# EGS002.net
KiCad netlist of a schematic drawn in Altium Designer
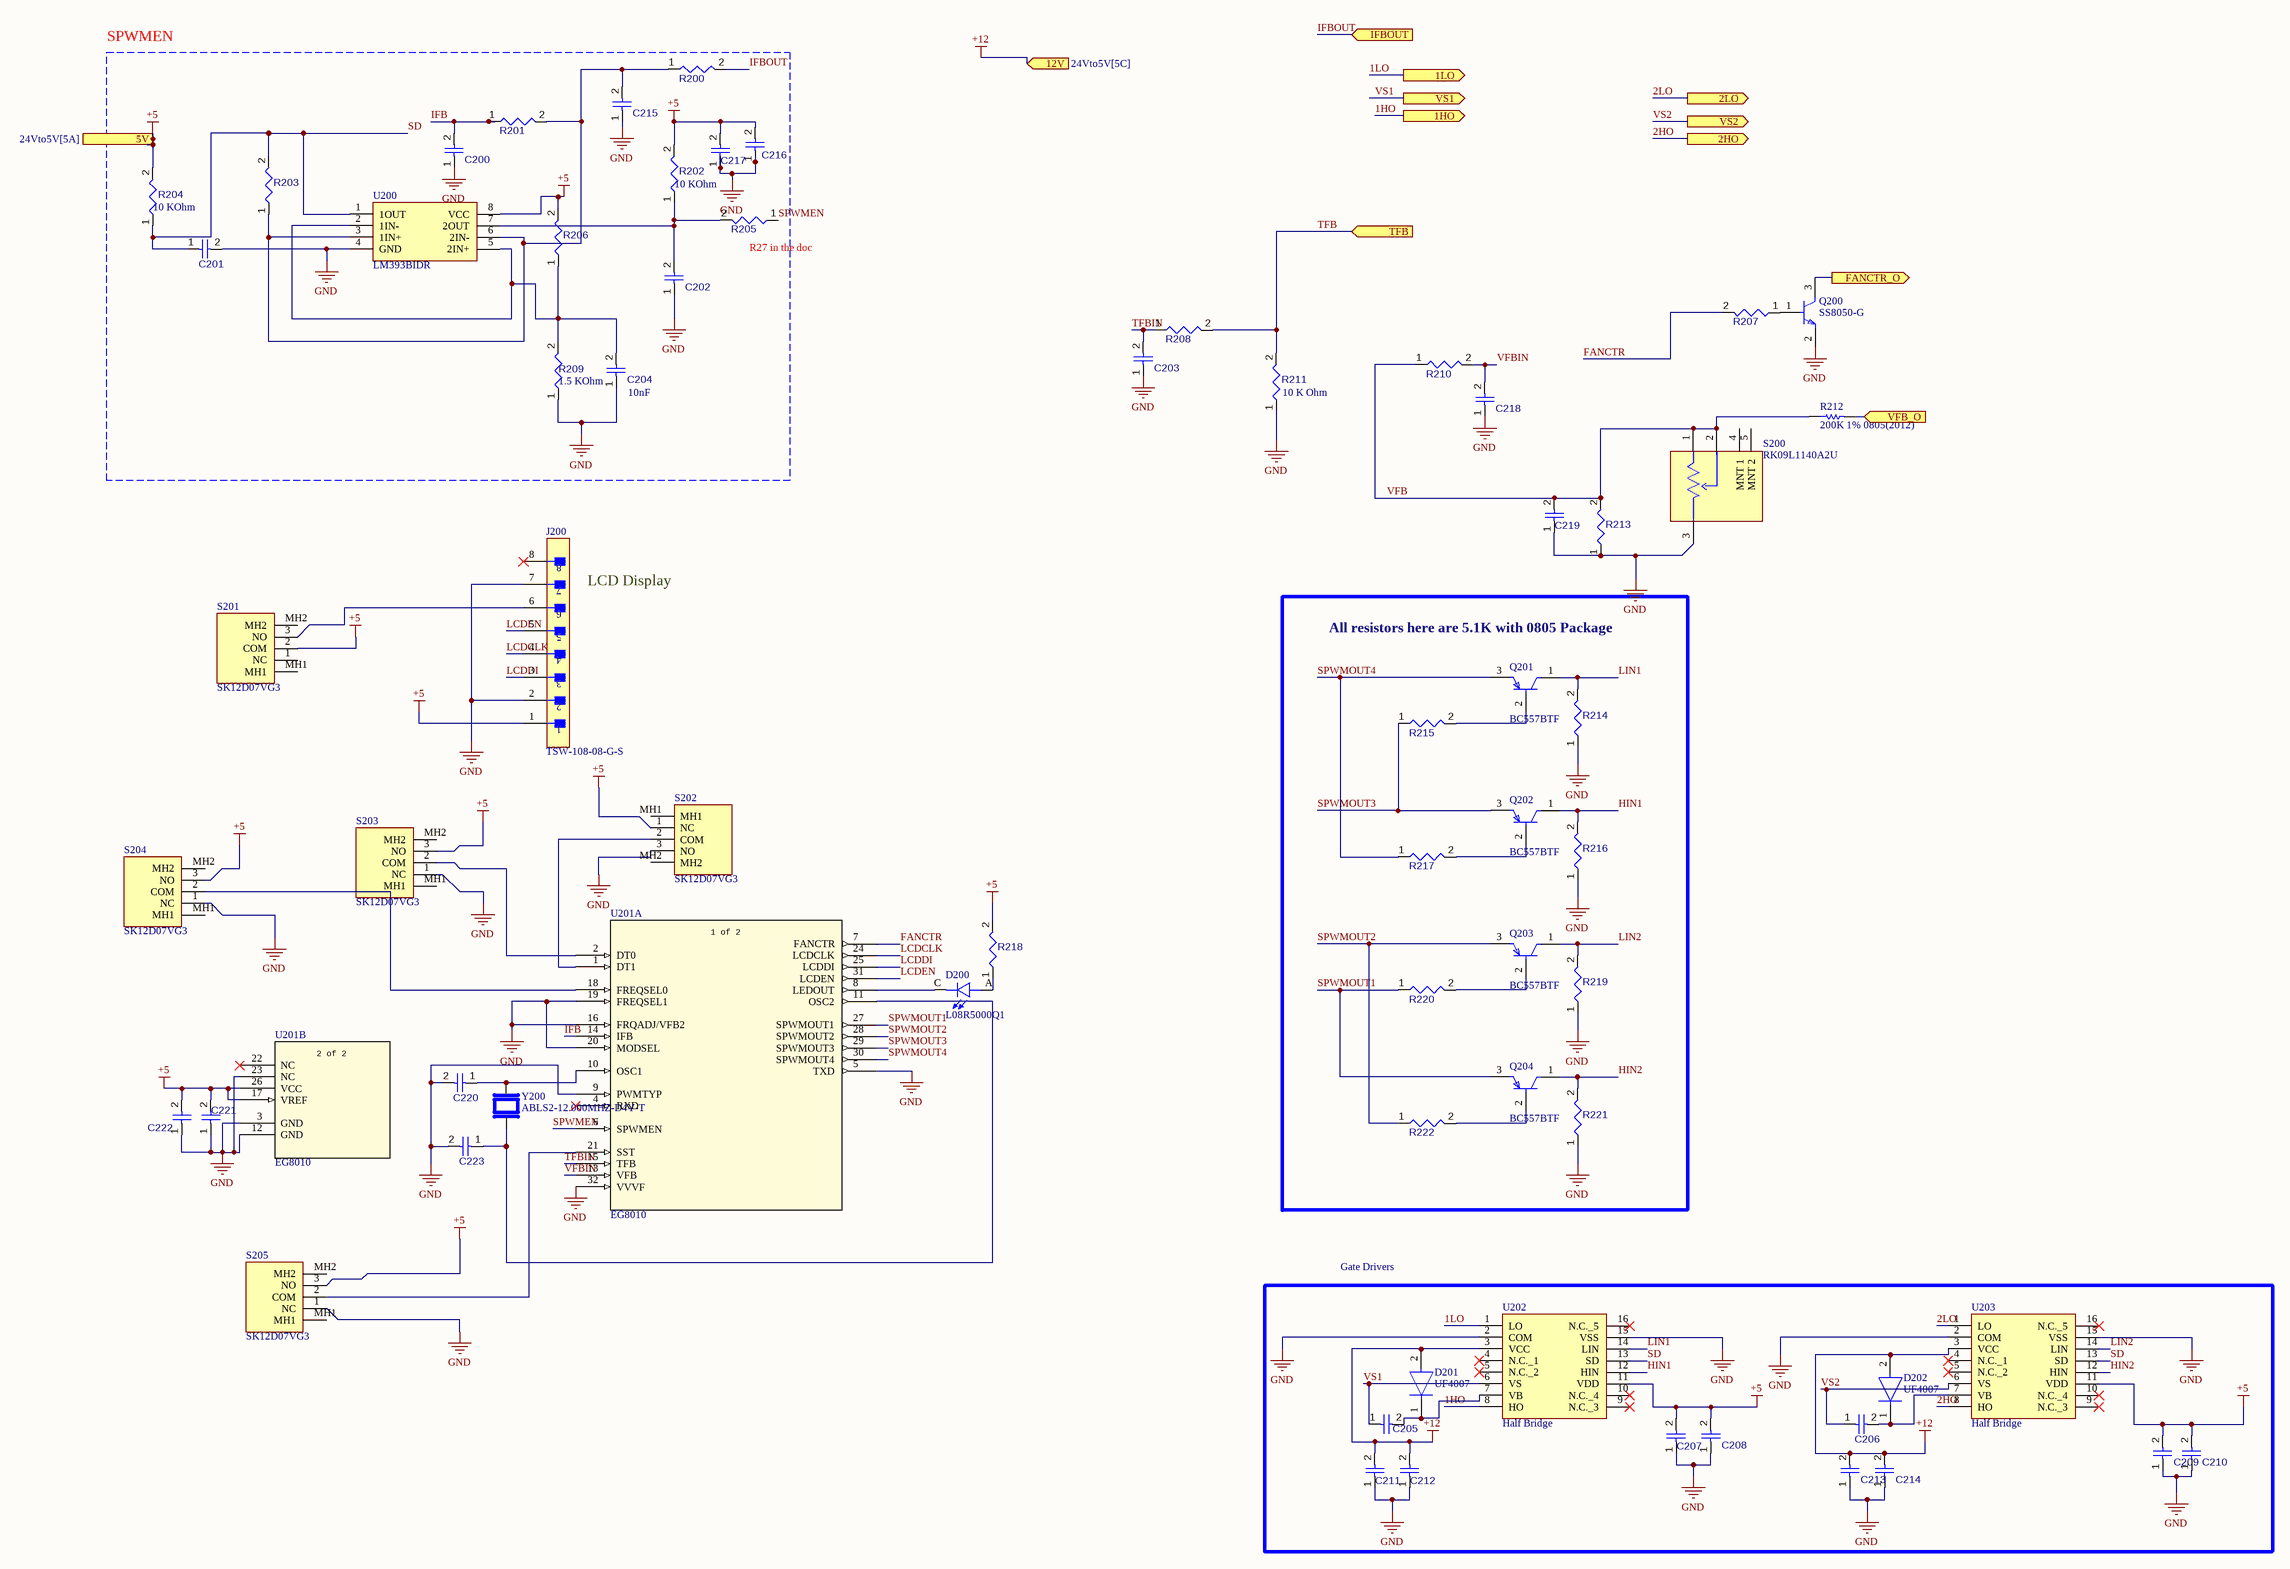
[diagram p0: EGS002.SchDoc]

(export (version "E")
  (design (tool "Eeschema 10.0.6"))
  (components
    (comp (ref "C200")
      (value "Capacitor 10nF +/-20% 50V 0402")
      (footprint "CAPC0402(1005)60_L")
      (description "Chip Capacitor, 10nF +/-20%, 50V, 0402, Thickness 0.6 mm")
      (fields (field (name "TOLERANCE") "5%"))
      (libsource (lib "Rahulb 23") (part "CAP-NP-2"))
    )
    (comp (ref "C201")
      (value "Capacitor 1nF +/-20% 50V 0402")
      (footprint "CAPC0402(1005)33_L")
      (description "Chip Capacitor, 1nF +/-20%, 50V, 0402, Thickness 0.33 mm")
      (fields (field (name "TOLERANCE") "10%"))
      (libsource (lib "Rahulb 23") (part "CAP-NP-2"))
    )
    (comp (ref "C202")
      (value "Capacitor 1nF +/-20% 50V 0402")
      (footprint "CAPC0402(1005)33_L")
      (description "Chip Capacitor, 1nF +/-20%, 50V, 0402, Thickness 0.33 mm")
      (fields (field (name "TOLERANCE") "10%"))
      (libsource (lib "Rahulb 23") (part "CAP-NP-2"))
    )
    (comp (ref "C203")
      (value "Capacitor 100 nF +/-10% 50 V 0805")
      (footprint "CAPC2013X95X50LL10T25")
      (description "Chip Capacitor, 100 nF, +/- 10%, 50 V, 0805 (2012 Metric)")
      (fields (field (name "TOLERANCE") "10%"))
      (libsource (lib "Rahulb 23") (part "CAP-NP-2"))
    )
    (comp (ref "C204")
      (value "Capacitor 10nF +/-20% 50V 0402")
      (footprint "CAPC0402(1005)60_L")
      (description "Chip Capacitor, 10nF +/-20%, 50V, 0402, Thickness 0.6 mm")
      (fields (field (name "TOLERANCE") "5%"))
      (libsource (lib "Rahulb 23") (part "CAP-NP-2"))
    )
    (comp (ref "C205")
      (value "Capacitor 10 uF +/- 10% 16 V 0805")
      (footprint "CAPC2013X135X45NL10T25")
      (description "Chip Capacitor, 10 uF, +/- 10%, 16 V, 0805 (2012 Metric)")
      (fields (field (name "TOLERANCE") "10%"))
      (libsource (lib "Rahulb 23") (part "CAP-NP-2"))
    )
    (comp (ref "C206")
      (value "Capacitor 10 uF +/- 10% 16 V 1206")
      (footprint "CAPC3216X180X50NL20T25")
      (description "Chip Capacitor, 10 uF, +/- 10%, 16 V, 1206 (3216 Metric)")
      (fields (field (name "TOLERANCE") "10%"))
      (libsource (lib "Rahulb 23") (part "CAP-NP-2"))
    )
    (comp (ref "C207")
      (value "Capacitor 100 nF +/-10% 50 V 0805")
      (footprint "CAPC2013X95X50LL10T25")
      (description "Chip Capacitor, 100 nF, +/- 10%, 50 V, 0805 (2012 Metric)")
      (fields (field (name "TOLERANCE") "10%"))
      (libsource (lib "Rahulb 23") (part "CAP-NP-2"))
    )
    (comp (ref "C208")
      (value "Capacitor 10 uF +/- 10% 16 V 1206")
      (footprint "CAPC3216X180X50NL20T25")
      (description "Chip Capacitor, 10 uF, +/- 10%, 16 V, 1206 (3216 Metric)")
      (fields (field (name "TOLERANCE") "10%"))
      (libsource (lib "Rahulb 23") (part "CAP-NP-2"))
    )
    (comp (ref "C209")
      (value "Capacitor 100 nF +/-10% 50 V 0805")
      (footprint "CAPC2013X95X50LL10T25")
      (description "Chip Capacitor, 100 nF, +/- 10%, 50 V, 0805 (2012 Metric)")
      (fields (field (name "TOLERANCE") "10%"))
      (libsource (lib "Rahulb 23") (part "CAP-NP-2"))
    )
    (comp (ref "C210")
      (value "Capacitor 10 uF +/- 10% 16 V 1206")
      (footprint "CAPC3216X180X50NL20T25")
      (description "Chip Capacitor, 10 uF, +/- 10%, 16 V, 1206 (3216 Metric)")
      (fields (field (name "TOLERANCE") "10%"))
      (libsource (lib "Rahulb 23") (part "CAP-NP-2"))
    )
    (comp (ref "C211")
      (value "Capacitor 100 nF +/-10% 50 V 0805")
      (footprint "CAPC2013X95X50LL10T25")
      (description "Chip Capacitor, 100 nF, +/- 10%, 50 V, 0805 (2012 Metric)")
      (fields (field (name "TOLERANCE") "10%"))
      (libsource (lib "Rahulb 23") (part "CAP-NP-2"))
    )
    (comp (ref "C212")
      (value "Capacitor 10 uF +/- 10% 16 V 1206")
      (footprint "CAPC3216X180X50NL20T25")
      (description "Chip Capacitor, 10 uF, +/- 10%, 16 V, 1206 (3216 Metric)")
      (fields (field (name "TOLERANCE") "10%"))
      (libsource (lib "Rahulb 23") (part "CAP-NP-2"))
    )
    (comp (ref "C213")
      (value "Capacitor 100 nF +/-10% 50 V 0805")
      (footprint "CAPC2013X95X50LL10T25")
      (description "Chip Capacitor, 100 nF, +/- 10%, 50 V, 0805 (2012 Metric)")
      (fields (field (name "TOLERANCE") "10%"))
      (libsource (lib "Rahulb 23") (part "CAP-NP-2"))
    )
    (comp (ref "C214")
      (value "Capacitor 10 uF +/- 10% 16 V 1206")
      (footprint "CAPC3216X180X50NL20T25")
      (description "Chip Capacitor, 10 uF, +/- 10%, 16 V, 1206 (3216 Metric)")
      (fields (field (name "TOLERANCE") "10%"))
      (libsource (lib "Rahulb 23") (part "CAP-NP-2"))
    )
    (comp (ref "C215")
      (value "Capacitor 1nF +/-20% 50V 0402")
      (footprint "CAPC0402(1005)33_L")
      (description "Chip Capacitor, 1nF +/-20%, 50V, 0402, Thickness 0.33 mm")
      (fields (field (name "TOLERANCE") "10%"))
      (libsource (lib "Rahulb 23") (part "CAP-NP-2"))
    )
    (comp (ref "C216")
      (value "Capacitor 10 uF +/- 10% 16 V 1206")
      (footprint "CAPC3216X180X50NL20T25")
      (description "Chip Capacitor, 10 uF, +/- 10%, 16 V, 1206 (3216 Metric)")
      (fields (field (name "TOLERANCE") "10%"))
      (libsource (lib "Rahulb 23") (part "CAP-NP-2"))
    )
    (comp (ref "C217")
      (value "Capacitor 100 nF +/-10% 50 V 0805")
      (footprint "CAPC2013X95X50LL10T25")
      (description "Chip Capacitor, 100 nF, +/- 10%, 50 V, 0805 (2012 Metric)")
      (fields (field (name "TOLERANCE") "10%"))
      (libsource (lib "Rahulb 23") (part "CAP-NP-2"))
    )
    (comp (ref "C218")
      (value "Capacitor 100 nF +/-10% 50 V 0805")
      (footprint "CAPC2013X95X50LL10T25")
      (description "Chip Capacitor, 100 nF, +/- 10%, 50 V, 0805 (2012 Metric)")
      (fields (field (name "TOLERANCE") "10%"))
      (libsource (lib "Rahulb 23") (part "CAP-NP-2"))
    )
    (comp (ref "C219")
      (value "Capacitor 100 nF +/-10% 50 V 0805")
      (footprint "CAPC2013X95X50LL10T25")
      (description "Chip Capacitor, 100 nF, +/- 10%, 50 V, 0805 (2012 Metric)")
      (fields (field (name "TOLERANCE") "10%"))
      (libsource (lib "Rahulb 23") (part "CAP-NP-2"))
    )
    (comp (ref "C220")
      (value "Capacitor 22pF +/-10% 50V 0402")
      (footprint "CAPC0402(1005)60_L")
      (description "Chip Capacitor, 22pF +/-10%, 50V, 0402, Thickness 0.6 mm")
      (fields (field (name "TOLERANCE") "10%"))
      (libsource (lib "Rahulb 23") (part "CAP-NP-2"))
    )
    (comp (ref "C221")
      (value "Capacitor 10 uF +/- 10% 16 V 1206")
      (footprint "CAPC3216X180X50NL20T25")
      (description "Chip Capacitor, 10 uF, +/- 10%, 16 V, 1206 (3216 Metric)")
      (fields (field (name "TOLERANCE") "10%"))
      (libsource (lib "Rahulb 23") (part "CAP-NP-2"))
    )
    (comp (ref "C222")
      (value "Capacitor 100 nF +/-10% 50 V 0805")
      (footprint "CAPC2013X95X50LL10T25")
      (description "Chip Capacitor, 100 nF, +/- 10%, 50 V, 0805 (2012 Metric)")
      (fields (field (name "TOLERANCE") "10%"))
      (libsource (lib "Rahulb 23") (part "CAP-NP-2"))
    )
    (comp (ref "C223")
      (value "Capacitor 22pF +/-10% 50V 0402")
      (footprint "CAPC0402(1005)60_L")
      (description "Chip Capacitor, 22pF +/-10%, 50V, 0402, Thickness 0.6 mm")
      (fields (field (name "TOLERANCE") "10%"))
      (libsource (lib "Rahulb 23") (part "CAP-NP-2"))
    )
    (comp (ref "D200")
      (value "L08R5000Q1")
      (footprint "LEDRD254W57D500H1070")
      (fields (field (name "MF") "LED Technology"))
      (libsource (lib "myComponents") (part "L08R5000Q1"))
    )
    (comp (ref "D201")
      (value "UF4007")
      (footprint "FP-017AH-MFG")
      (description "DIODE GEN PURP 1KV 1A DO41")
      (fields
        (field (name "MANUFACTURER") "ON Semiconductor")
        (field (name "OCTOPART") "https://octopart.com/uf4007-on+semiconductor-84331693")
      )
      (libsource (lib "Altium Content Vault") (part "d7152d700b627762746794eb795d46e"))
    )
    (comp (ref "D202")
      (value "UF4007")
      (footprint "FP-017AH-MFG")
      (description "DIODE GEN PURP 1KV 1A DO41")
      (fields
        (field (name "MANUFACTURER") "ON Semiconductor")
        (field (name "OCTOPART") "https://octopart.com/uf4007-on+semiconductor-84331693")
      )
      (libsource (lib "Altium Content Vault") (part "d7152d700b627762746794eb795d46e"))
    )
    (comp (ref "J200")
      (value "TSW-108-08-G-S")
      (footprint "FP-TSW-108-08-G-S-MFG")
      (description "CONN HEADER VERT 8POS 2.54MM")
      (fields
        (field (name "MANUFACTURER") "Samtec")
        (field (name "OCTOPART") "https://octopart.com/tsw-108-08-g-s-samtec-272653")
      )
      (libsource (lib "Altium Content Vault") (part "99ec2b232beb5d2356d4d77f6a047f0"))
    )
    (comp (ref "Q200")
      (value "SS8050-G")
      (footprint "FP-SS8050-G-MFG")
      (description "NPN TRANSISTOR 1.5A 40V SOT-23 R")
      (libsource (lib "Altium Content Vault") (part "2a1388f82443b098dcd57d24ac7632d"))
    )
    (comp (ref "Q201")
      (value "BC557BTF")
      (footprint "FP-135AR-MFG")
      (description "BC557BTF Small Signal Bipolar Transistor, 0.1A I(C), 45V V(BR)CEO, 1-Element, PNP, Silicon, TO-92")
      (libsource (lib "Altium Content Vault") (part "9e2844d3eb996af6824d2c99fe21afc"))
    )
    (comp (ref "Q202")
      (value "BC557BTF")
      (footprint "FP-135AR-MFG")
      (description "BC557BTF Small Signal Bipolar Transistor, 0.1A I(C), 45V V(BR)CEO, 1-Element, PNP, Silicon, TO-92")
      (libsource (lib "Altium Content Vault") (part "9e2844d3eb996af6824d2c99fe21afc"))
    )
    (comp (ref "Q203")
      (value "BC557BTF")
      (footprint "FP-135AR-MFG")
      (description "BC557BTF Small Signal Bipolar Transistor, 0.1A I(C), 45V V(BR)CEO, 1-Element, PNP, Silicon, TO-92")
      (libsource (lib "Altium Content Vault") (part "9e2844d3eb996af6824d2c99fe21afc"))
    )
    (comp (ref "Q204")
      (value "BC557BTF")
      (footprint "FP-135AR-MFG")
      (description "BC557BTF Small Signal Bipolar Transistor, 0.1A I(C), 45V V(BR)CEO, 1-Element, PNP, Silicon, TO-92")
      (libsource (lib "Altium Content Vault") (part "9e2844d3eb996af6824d2c99fe21afc"))
    )
    (comp (ref "R200")
      (value "Resistor 1K +/-5% 0805 125 mW")
      (footprint "RESC0805(2012)_L")
      (description "Chip Resistor, 1 kOhms, +/-5%, 125 mW, -55 to 155 degC, 0805")
      (fields (field (name "TOLERANCE") "5%") (field (name "POWER") "125mW"))
      (libsource (lib "Rahulb 23") (part "RES-2"))
    )
    (comp (ref "R201")
      (value "Resistor 100k +/-1% 0805 125 mW")
      (footprint "RESC2013X70X40ML20T20")
      (description "Chip Resistor, 100 KOhm, +/- 1%, 0.125 W, -55 to 155 degC, 0805 (2012 Metric)")
      (fields (field (name "TOLERANCE") "1%") (field (name "POWER") "125mW"))
      (libsource (lib "Rahulb 23") (part "RES-2"))
    )
    (comp (ref "R202")
      (value "Resistor 10k +/-1% 0805 125 mW")
      (footprint "RESC2013X50X35ML15T15")
      (description "Chip Resistor, 10 KOhm, +/- 1%, 125 mW, -55 to 155 degC, 0805 (2012 Metric)")
      (fields (field (name "TOLERANCE") "1%") (field (name "POWER") "125mW"))
      (libsource (lib "Rahulb 23") (part "RES-2"))
    )
    (comp (ref "R203")
      (value "Resistor 100k +/-1% 0805 125 mW")
      (footprint "RESC2013X70X40ML20T20")
      (description "Chip Resistor, 100 KOhm, +/- 1%, 0.125 W, -55 to 155 degC, 0805 (2012 Metric)")
      (fields (field (name "TOLERANCE") "1%") (field (name "POWER") "125mW"))
      (libsource (lib "Rahulb 23") (part "RES-2"))
    )
    (comp (ref "R204")
      (value "Resistor 10k +/-1% 0805 125 mW")
      (footprint "RESC2013X50X35ML15T15")
      (description "Chip Resistor, 10 KOhm, +/- 1%, 125 mW, -55 to 155 degC, 0805 (2012 Metric)")
      (fields (field (name "TOLERANCE") "1%") (field (name "POWER") "125mW"))
      (libsource (lib "Rahulb 23") (part "RES-2"))
    )
    (comp (ref "R205")
      (value "Resistor 1.5k +/-1% 0805 125 mW")
      (footprint "RESC2013X50X35ML15T15")
      (description "Chip Resistor, 1.5 KOhm, +/- 1%, 125 mW, -55 to 155 degC, 0805 (2012 Metric)")
      (fields (field (name "TOLERANCE") "1%") (field (name "POWER") "125mW"))
      (libsource (lib "Rahulb 23") (part "RES-2"))
    )
    (comp (ref "R206")
      (value "Resistor 10k +/-1% 0805 125 mW")
      (footprint "RESC2013X50X35ML15T15")
      (description "Chip Resistor, 10 KOhm, +/- 1%, 125 mW, -55 to 155 degC, 0805 (2012 Metric)")
      (fields (field (name "TOLERANCE") "1%") (field (name "POWER") "125mW"))
      (libsource (lib "Rahulb 23") (part "RES-2"))
    )
    (comp (ref "R207")
      (value "Resistor 1.5k +/-1% 0805 125 mW")
      (footprint "RESC2013X50X35ML15T15")
      (description "Chip Resistor, 1.5 KOhm, +/- 1%, 125 mW, -55 to 155 degC, 0805 (2012 Metric)")
      (fields (field (name "TOLERANCE") "1%") (field (name "POWER") "125mW"))
      (libsource (lib "Rahulb 23") (part "RES-2"))
    )
    (comp (ref "R208")
      (value "Resistor 100R +/-1 % 0402 63 mW")
      (footprint "RESC0402(1005)_L")
      (description "Chip Resistor, 100 Ohms, +/-1 %, 63 mW, -55 to 155 degC, 0402")
      (fields (field (name "TOLERANCE") "1%") (field (name "POWER") "63mW"))
      (libsource (lib "Rahulb 23") (part "RES-2"))
    )
    (comp (ref "R209")
      (value "Resistor 1.5k +/-1% 0805 125 mW")
      (footprint "RESC2013X50X35ML15T15")
      (description "Chip Resistor, 1.5 KOhm, +/- 1%, 125 mW, -55 to 155 degC, 0805 (2012 Metric)")
      (fields (field (name "TOLERANCE") "1%") (field (name "POWER") "125mW"))
      (libsource (lib "Rahulb 23") (part "RES-2"))
    )
    (comp (ref "R210")
      (value "Resistor 100R +/-1 % 0402 63 mW")
      (footprint "RESC0402(1005)_L")
      (description "Chip Resistor, 100 Ohms, +/-1 %, 63 mW, -55 to 155 degC, 0402")
      (fields (field (name "TOLERANCE") "1%") (field (name "POWER") "63mW"))
      (libsource (lib "Rahulb 23") (part "RES-2"))
    )
    (comp (ref "R211")
      (value "Resistor 10k +/-1% 0805 125 mW")
      (footprint "RESC2013X50X35ML15T15")
      (description "Chip Resistor, 10 KOhm, +/- 1%, 125 mW, -55 to 155 degC, 0805 (2012 Metric)")
      (fields (field (name "TOLERANCE") "1%") (field (name "POWER") "125mW"))
      (libsource (lib "Rahulb 23") (part "RES-2"))
    )
    (comp (ref "R212")
      (value "200K 1% 0805(2012)")
      (footprint "RESC0805(2012)_N")
      (description "200K 0.125W 1% 0805 (2012 Metric)  SMD")
      (fields (field (name "POWER") "0.125 W") (field (name "TOLERANCE") "1 %"))
      (libsource (lib "Altium Content Vault") (part "RES"))
    )
    (comp (ref "R213")
      (value "Resistor 10k +/-1% 0805 125 mW")
      (footprint "RESC2013X50X35ML15T15")
      (description "Chip Resistor, 10 KOhm, +/- 1%, 125 mW, -55 to 155 degC, 0805 (2012 Metric)")
      (fields (field (name "TOLERANCE") "1%") (field (name "POWER") "125mW"))
      (libsource (lib "Rahulb 23") (part "RES-2"))
    )
    (comp (ref "R214")
      (value "Resistor 5.1k +/-1% 0805 125 mW")
      (footprint "RESC2013X50X35ML15T15")
      (description "Chip Resistor, 5.1 KOhm, +/- 1%, 125 mW, -55 to 155 degC, 0805 (2012 Metric)")
      (fields (field (name "TOLERANCE") "1%") (field (name "POWER") "125mW"))
      (libsource (lib "Rahulb 23") (part "RES-2"))
    )
    (comp (ref "R215")
      (value "Resistor 5.1k +/-1% 0805 125 mW")
      (footprint "RESC2013X50X35ML15T15")
      (description "Chip Resistor, 5.1 KOhm, +/- 1%, 125 mW, -55 to 155 degC, 0805 (2012 Metric)")
      (fields (field (name "TOLERANCE") "1%") (field (name "POWER") "125mW"))
      (libsource (lib "Rahulb 23") (part "RES-2"))
    )
    (comp (ref "R216")
      (value "Resistor 5.1k +/-1% 0805 125 mW")
      (footprint "RESC2013X50X35ML15T15")
      (description "Chip Resistor, 5.1 KOhm, +/- 1%, 125 mW, -55 to 155 degC, 0805 (2012 Metric)")
      (fields (field (name "TOLERANCE") "1%") (field (name "POWER") "125mW"))
      (libsource (lib "Rahulb 23") (part "RES-2"))
    )
    (comp (ref "R217")
      (value "Resistor 5.1k +/-1% 0805 125 mW")
      (footprint "RESC2013X50X35ML15T15")
      (description "Chip Resistor, 5.1 KOhm, +/- 1%, 125 mW, -55 to 155 degC, 0805 (2012 Metric)")
      (fields (field (name "TOLERANCE") "1%") (field (name "POWER") "125mW"))
      (libsource (lib "Rahulb 23") (part "RES-2"))
    )
    (comp (ref "R218")
      (value "Resistor 1K +/-5% 0805 125 mW")
      (footprint "RESC0805(2012)_L")
      (description "Chip Resistor, 1 kOhms, +/-5%, 125 mW, -55 to 155 degC, 0805")
      (fields (field (name "TOLERANCE") "5%") (field (name "POWER") "125mW"))
      (libsource (lib "Rahulb 23") (part "RES-2"))
    )
    (comp (ref "R219")
      (value "Resistor 5.1k +/-1% 0805 125 mW")
      (footprint "RESC2013X50X35ML15T15")
      (description "Chip Resistor, 5.1 KOhm, +/- 1%, 125 mW, -55 to 155 degC, 0805 (2012 Metric)")
      (fields (field (name "TOLERANCE") "1%") (field (name "POWER") "125mW"))
      (libsource (lib "Rahulb 23") (part "RES-2"))
    )
    (comp (ref "R220")
      (value "Resistor 5.1k +/-1% 0805 125 mW")
      (footprint "RESC2013X50X35ML15T15")
      (description "Chip Resistor, 5.1 KOhm, +/- 1%, 125 mW, -55 to 155 degC, 0805 (2012 Metric)")
      (fields (field (name "TOLERANCE") "1%") (field (name "POWER") "125mW"))
      (libsource (lib "Rahulb 23") (part "RES-2"))
    )
    (comp (ref "R221")
      (value "Resistor 5.1k +/-1% 0805 125 mW")
      (footprint "RESC2013X50X35ML15T15")
      (description "Chip Resistor, 5.1 KOhm, +/- 1%, 125 mW, -55 to 155 degC, 0805 (2012 Metric)")
      (fields (field (name "TOLERANCE") "1%") (field (name "POWER") "125mW"))
      (libsource (lib "Rahulb 23") (part "RES-2"))
    )
    (comp (ref "R222")
      (value "Resistor 5.1k +/-1% 0805 125 mW")
      (footprint "RESC2013X50X35ML15T15")
      (description "Chip Resistor, 5.1 KOhm, +/- 1%, 125 mW, -55 to 155 degC, 0805 (2012 Metric)")
      (fields (field (name "TOLERANCE") "1%") (field (name "POWER") "125mW"))
      (libsource (lib "Rahulb 23") (part "RES-2"))
    )
    (comp (ref "S200")
      (value "RK09L1140A2U")
      (footprint "FP-RK09L1140A2U-MFG")
      (description "9mm Size Metal Shaft Snap-in Type RK09L Series")
      (fields
        (field (name "TOLERANCE") "20%")
        (field (name "OCTOPART") "https://octopart.com/rk09l1140a2u-alps-7850070")
      )
      (libsource (lib "Altium Content Vault") (part "0c568a6e0ac31b8b52ae5f6704acd43"))
    )
    (comp (ref "S201")
      (value "SK12D07VG3")
      (footprint "SamacSys:SK12D07VG3")
      (description "Switch")
      (libsource (lib "*") (part "SK12D07VG3"))
    )
    (comp (ref "S202")
      (value "SK12D07VG3")
      (footprint "SamacSys:SK12D07VG3")
      (description "Switch")
      (libsource (lib "") (part "SK12D07VG3_1"))
    )
    (comp (ref "S203")
      (value "SK12D07VG3")
      (footprint "SamacSys:SK12D07VG3")
      (description "Switch")
      (libsource (lib "*") (part "SK12D07VG3"))
    )
    (comp (ref "S204")
      (value "SK12D07VG3")
      (footprint "SamacSys:SK12D07VG3")
      (description "Switch")
      (libsource (lib "*") (part "SK12D07VG3"))
    )
    (comp (ref "S205")
      (value "SK12D07VG3")
      (footprint "SamacSys:SK12D07VG3")
      (description "Switch")
      (libsource (lib "*") (part "SK12D07VG3"))
    )
    (comp (ref "U200")
      (value "LM393BIDR")
      (description "Analog Comparators Dual standard comparator 8-SOIC -40 to 85")
      (fields (field (name "MOUSER PART NUMBER") "595-LM393BIDR"))
      (libsource (lib "myComponents") (part "LM393BIDR"))
    )
    (comp (ref "U201")
      (value "EG8010")
      (description "Description")
      (fields (field (name "COPYRIGHT") "Copyright (C) 2026 Ultra Librarian. All rights reserved."))
      (libsource (lib "myComponents") (part "EG8010"))
    )
    (comp (ref "U202")
      (value "Half Bridge")
      (footprint "IR2110S")
      (libsource (lib "myComponents") (part "IR2110S"))
    )
    (comp (ref "U203")
      (value "Half Bridge")
      (footprint "IR2110S")
      (libsource (lib "myComponents") (part "IR2110S"))
    )
    (comp (ref "Y200")
      (value "ABLS2-12.000MHZ-D4Y-T")
      (footprint "XTAL_ABLS2-12.000MHZ-D4Y-T")
      (description "HC/49US (AT49) LOW PROFILE SURFACE MOUNT MICROPROCESSOR CRYSTAL")
      (fields (field (name "MF") "Abracon"))
      (libsource (lib "myComponents") (part "ABLS2-12.000MHZ-D4Y-T"))
    )
  )
  (nets
    (net (code "1") (name "+5") (class "Default")
      (node (ref "C207") (pin "2") (pinfunction "2_2") (pintype "passive"))
      (node (ref "C208") (pin "2") (pinfunction "2_2") (pintype "passive"))
      (node (ref "C209") (pin "2") (pinfunction "2_2") (pintype "passive"))
      (node (ref "C210") (pin "2") (pinfunction "2_2") (pintype "passive"))
      (node (ref "C216") (pin "2") (pinfunction "2_2") (pintype "passive"))
      (node (ref "C217") (pin "2") (pinfunction "2_2") (pintype "passive"))
      (node (ref "C221") (pin "2") (pinfunction "2_2") (pintype "passive"))
      (node (ref "C222") (pin "2") (pinfunction "2_2") (pintype "passive"))
      (node (ref "J200") (pin "1") (pinfunction "1_1") (pintype "passive"))
      (node (ref "R202") (pin "2") (pinfunction "2_2") (pintype "passive"))
      (node (ref "R204") (pin "2") (pinfunction "2_2") (pintype "passive"))
      (node (ref "R206") (pin "2") (pinfunction "2_2") (pintype "passive"))
      (node (ref "R218") (pin "2") (pinfunction "2_2") (pintype "passive"))
      (node (ref "S201") (pin "2") (pinfunction "COM_2") (pintype "passive"))
      (node (ref "S202") (pin "1") (pinfunction "NC_1") (pintype "passive"))
      (node (ref "S203") (pin "3") (pinfunction "NO_3") (pintype "passive"))
      (node (ref "S204") (pin "3") (pinfunction "NO_3") (pintype "passive"))
      (node (ref "S205") (pin "3") (pinfunction "NO_3") (pintype "passive"))
      (node (ref "U200") (pin "8") (pinfunction "VCC_8") (pintype "passive"))
      (node (ref "U201") (pin "17") (pinfunction "VREF_17") (pintype "input"))
      (node (ref "U201") (pin "26") (pinfunction "VCC_26") (pintype "power_in"))
      (node (ref "U202") (pin "11") (pinfunction "VDD_11") (pintype "passive"))
      (node (ref "U203") (pin "11") (pinfunction "VDD_11") (pintype "passive"))
    )
    (net (code "2") (name "+12") (class "Default")
      (node (ref "C211") (pin "2") (pinfunction "2_2") (pintype "passive"))
      (node (ref "C212") (pin "2") (pinfunction "2_2") (pintype "passive"))
      (node (ref "C213") (pin "2") (pinfunction "2_2") (pintype "passive"))
      (node (ref "C214") (pin "2") (pinfunction "2_2") (pintype "passive"))
      (node (ref "D201") (pin "2") (pinfunction "A_2") (pintype "passive"))
      (node (ref "D202") (pin "2") (pinfunction "A_2") (pintype "passive"))
      (node (ref "U202") (pin "3") (pinfunction "VCC_3") (pintype "passive"))
      (node (ref "U203") (pin "3") (pinfunction "VCC_3") (pintype "passive"))
    )
    (net (code "3") (name "/1HO") (class "Default")
      (node (ref "U202") (pin "8") (pinfunction "HO_8") (pintype "passive"))
    )
    (net (code "4") (name "/1LO") (class "Default")
      (node (ref "U202") (pin "1") (pinfunction "LO_1") (pintype "passive"))
    )
    (net (code "5") (name "/2HO") (class "Default")
      (node (ref "U203") (pin "8") (pinfunction "HO_8") (pintype "passive"))
    )
    (net (code "6") (name "/2LO") (class "Default")
      (node (ref "U203") (pin "1") (pinfunction "LO_1") (pintype "passive"))
    )
    (net (code "7") (name "/FANCTR") (class "Default")
      (node (ref "R207") (pin "2") (pinfunction "2_2") (pintype "passive"))
      (node (ref "U201") (pin "7") (pinfunction "FANCTR_7") (pintype "output"))
    )
    (net (code "8") (name "/FANCTR_O") (class "Default")
      (node (ref "Q200") (pin "3") (pinfunction "C_3") (pintype "passive"))
    )
    (net (code "9") (name "/HIN1") (class "Default")
      (node (ref "Q202") (pin "1") (pinfunction "C_1") (pintype "passive"))
      (node (ref "R216") (pin "2") (pinfunction "2_2") (pintype "passive"))
      (node (ref "U202") (pin "12") (pinfunction "HIN_12") (pintype "passive"))
    )
    (net (code "10") (name "/HIN2") (class "Default")
      (node (ref "Q204") (pin "1") (pinfunction "C_1") (pintype "passive"))
      (node (ref "R221") (pin "2") (pinfunction "2_2") (pintype "passive"))
      (node (ref "U203") (pin "12") (pinfunction "HIN_12") (pintype "passive"))
    )
    (net (code "11") (name "/IFB") (class "Default")
      (node (ref "C200") (pin "2") (pinfunction "2_2") (pintype "passive"))
      (node (ref "R201") (pin "1") (pinfunction "1_1") (pintype "passive"))
      (node (ref "U201") (pin "14") (pinfunction "IFB_14") (pintype "input"))
    )
    (net (code "12") (name "/IFBOUT") (class "Default")
      (node (ref "R200") (pin "2") (pinfunction "2_2") (pintype "passive"))
    )
    (net (code "13") (name "/LCDCLK") (class "Default")
      (node (ref "J200") (pin "4") (pinfunction "4_4") (pintype "passive"))
      (node (ref "U201") (pin "24") (pinfunction "LCDCLK_24") (pintype "output"))
    )
    (net (code "14") (name "/LCDDI") (class "Default")
      (node (ref "J200") (pin "3") (pinfunction "3_3") (pintype "passive"))
      (node (ref "U201") (pin "25") (pinfunction "LCDDI_25") (pintype "output"))
    )
    (net (code "15") (name "/LCDEN") (class "Default")
      (node (ref "J200") (pin "5") (pinfunction "5_5") (pintype "passive"))
      (node (ref "U201") (pin "31") (pinfunction "LCDEN_31") (pintype "output"))
    )
    (net (code "16") (name "/LIN1") (class "Default")
      (node (ref "Q201") (pin "1") (pinfunction "C_1") (pintype "passive"))
      (node (ref "R214") (pin "2") (pinfunction "2_2") (pintype "passive"))
      (node (ref "U202") (pin "14") (pinfunction "LIN_14") (pintype "passive"))
    )
    (net (code "17") (name "/LIN2") (class "Default")
      (node (ref "Q203") (pin "1") (pinfunction "C_1") (pintype "passive"))
      (node (ref "R219") (pin "2") (pinfunction "2_2") (pintype "passive"))
      (node (ref "U203") (pin "14") (pinfunction "LIN_14") (pintype "passive"))
    )
    (net (code "18") (name "/SD") (class "Default")
      (node (ref "C201") (pin "1") (pinfunction "1_1") (pintype "passive"))
      (node (ref "R203") (pin "2") (pinfunction "2_2") (pintype "passive"))
      (node (ref "R204") (pin "1") (pinfunction "1_1") (pintype "passive"))
      (node (ref "U200") (pin "1") (pinfunction "1OUT_1") (pintype "passive"))
      (node (ref "U202") (pin "13") (pinfunction "SD_13") (pintype "passive"))
      (node (ref "U203") (pin "13") (pinfunction "SD_13") (pintype "passive"))
    )
    (net (code "19") (name "/SPWMEN") (class "Default")
      (node (ref "R205") (pin "1") (pinfunction "1_1") (pintype "passive"))
      (node (ref "U201") (pin "6") (pinfunction "SPWMEN_6") (pintype "input"))
    )
    (net (code "20") (name "/SPWMOUT1") (class "Default")
      (node (ref "Q204") (pin "3") (pinfunction "E_3") (pintype "passive"))
      (node (ref "R220") (pin "1") (pinfunction "1_1") (pintype "passive"))
      (node (ref "U201") (pin "27") (pinfunction "SPWMOUT1_27") (pintype "output"))
    )
    (net (code "21") (name "/SPWMOUT2") (class "Default")
      (node (ref "Q203") (pin "3") (pinfunction "E_3") (pintype "passive"))
      (node (ref "R222") (pin "1") (pinfunction "1_1") (pintype "passive"))
      (node (ref "U201") (pin "28") (pinfunction "SPWMOUT2_28") (pintype "output"))
    )
    (net (code "22") (name "/SPWMOUT3") (class "Default")
      (node (ref "Q202") (pin "3") (pinfunction "E_3") (pintype "passive"))
      (node (ref "R215") (pin "1") (pinfunction "1_1") (pintype "passive"))
      (node (ref "U201") (pin "29") (pinfunction "SPWMOUT3_29") (pintype "output"))
    )
    (net (code "23") (name "/SPWMOUT4") (class "Default")
      (node (ref "Q201") (pin "3") (pinfunction "E_3") (pintype "passive"))
      (node (ref "R217") (pin "1") (pinfunction "1_1") (pintype "passive"))
      (node (ref "U201") (pin "30") (pinfunction "SPWMOUT4_30") (pintype "output"))
    )
    (net (code "24") (name "/TFB") (class "Default")
      (node (ref "R208") (pin "2") (pinfunction "2_2") (pintype "passive"))
      (node (ref "R211") (pin "2") (pinfunction "2_2") (pintype "passive"))
    )
    (net (code "25") (name "/TFBIN") (class "Default")
      (node (ref "C203") (pin "2") (pinfunction "2_2") (pintype "passive"))
      (node (ref "R208") (pin "1") (pinfunction "1_1") (pintype "passive"))
      (node (ref "U201") (pin "15") (pinfunction "TFB_15") (pintype "input"))
    )
    (net (code "26") (name "/VFB") (class "Default")
      (node (ref "C219") (pin "2") (pinfunction "2_2") (pintype "passive"))
      (node (ref "R210") (pin "1") (pinfunction "1_1") (pintype "passive"))
      (node (ref "R212") (pin "1") (pinfunction "1_1") (pintype "passive"))
      (node (ref "R213") (pin "2") (pinfunction "2_2") (pintype "passive"))
      (node (ref "S200") (pin "1") (pinfunction "1_1") (pintype "passive"))
      (node (ref "S200") (pin "2") (pinfunction "2_2") (pintype "passive"))
    )
    (net (code "27") (name "/VFBIN") (class "Default")
      (node (ref "C218") (pin "2") (pinfunction "2_2") (pintype "passive"))
      (node (ref "R210") (pin "2") (pinfunction "2_2") (pintype "passive"))
      (node (ref "U201") (pin "13") (pinfunction "VFB_13") (pintype "input"))
    )
    (net (code "28") (name "/VFB_O") (class "Default")
      (node (ref "R212") (pin "2") (pinfunction "2_2") (pintype "passive"))
    )
    (net (code "29") (name "/VS1") (class "Default")
      (node (ref "C205") (pin "1") (pinfunction "1_1") (pintype "passive"))
      (node (ref "U202") (pin "6") (pinfunction "VS_6") (pintype "passive"))
    )
    (net (code "30") (name "/VS2") (class "Default")
      (node (ref "C206") (pin "1") (pinfunction "1_1") (pintype "passive"))
      (node (ref "U203") (pin "6") (pinfunction "VS_6") (pintype "passive"))
    )
    (net (code "31") (name "GND") (class "Default")
      (node (ref "C200") (pin "1") (pinfunction "1_1") (pintype "passive"))
      (node (ref "C201") (pin "2") (pinfunction "2_2") (pintype "passive"))
      (node (ref "C202") (pin "1") (pinfunction "1_1") (pintype "passive"))
      (node (ref "C203") (pin "1") (pinfunction "1_1") (pintype "passive"))
      (node (ref "C204") (pin "1") (pinfunction "1_1") (pintype "passive"))
      (node (ref "C207") (pin "1") (pinfunction "1_1") (pintype "passive"))
      (node (ref "C208") (pin "1") (pinfunction "1_1") (pintype "passive"))
      (node (ref "C209") (pin "1") (pinfunction "1_1") (pintype "passive"))
      (node (ref "C210") (pin "1") (pinfunction "1_1") (pintype "passive"))
      (node (ref "C211") (pin "1") (pinfunction "1_1") (pintype "passive"))
      (node (ref "C212") (pin "1") (pinfunction "1_1") (pintype "passive"))
      (node (ref "C213") (pin "1") (pinfunction "1_1") (pintype "passive"))
      (node (ref "C214") (pin "1") (pinfunction "1_1") (pintype "passive"))
      (node (ref "C215") (pin "1") (pinfunction "1_1") (pintype "passive"))
      (node (ref "C216") (pin "1") (pinfunction "1_1") (pintype "passive"))
      (node (ref "C217") (pin "1") (pinfunction "1_1") (pintype "passive"))
      (node (ref "C218") (pin "1") (pinfunction "1_1") (pintype "passive"))
      (node (ref "C219") (pin "1") (pinfunction "1_1") (pintype "passive"))
      (node (ref "C220") (pin "2") (pinfunction "2_2") (pintype "passive"))
      (node (ref "C221") (pin "1") (pinfunction "1_1") (pintype "passive"))
      (node (ref "C222") (pin "1") (pinfunction "1_1") (pintype "passive"))
      (node (ref "C223") (pin "2") (pinfunction "2_2") (pintype "passive"))
      (node (ref "J200") (pin "2") (pinfunction "2_2") (pintype "passive"))
      (node (ref "J200") (pin "7") (pinfunction "7_7") (pintype "passive"))
      (node (ref "Q200") (pin "2") (pinfunction "E_2") (pintype "passive"))
      (node (ref "R209") (pin "1") (pinfunction "1_1") (pintype "passive"))
      (node (ref "R211") (pin "1") (pinfunction "1_1") (pintype "passive"))
      (node (ref "R213") (pin "1") (pinfunction "1_1") (pintype "passive"))
      (node (ref "R214") (pin "1") (pinfunction "1_1") (pintype "passive"))
      (node (ref "R216") (pin "1") (pinfunction "1_1") (pintype "passive"))
      (node (ref "R219") (pin "1") (pinfunction "1_1") (pintype "passive"))
      (node (ref "R221") (pin "1") (pinfunction "1_1") (pintype "passive"))
      (node (ref "S200") (pin "3") (pinfunction "3_3") (pintype "passive"))
      (node (ref "S202") (pin "3") (pinfunction "NO_3") (pintype "passive"))
      (node (ref "S203") (pin "1") (pinfunction "NC_1") (pintype "passive"))
      (node (ref "S204") (pin "1") (pinfunction "NC_1") (pintype "passive"))
      (node (ref "S205") (pin "1") (pinfunction "NC_1") (pintype "passive"))
      (node (ref "U200") (pin "4") (pinfunction "GND_4") (pintype "passive"))
      (node (ref "U201") (pin "12") (pinfunction "GND_12") (pintype "power_in"))
      (node (ref "U201") (pin "16") (pinfunction "FRQADJ/VFB2_16") (pintype "input"))
      (node (ref "U201") (pin "19") (pinfunction "FREQSEL1_19") (pintype "input"))
      (node (ref "U201") (pin "20") (pinfunction "MODSEL_20") (pintype "input"))
      (node (ref "U201") (pin "23") (pinfunction "NC_23") (pintype "passive"))
      (node (ref "U201") (pin "3") (pinfunction "GND_3") (pintype "power_in"))
      (node (ref "U201") (pin "32") (pinfunction "VVVF_32") (pintype "input"))
      (node (ref "U201") (pin "5") (pinfunction "TXD_5") (pintype "output"))
      (node (ref "U201") (pin "9") (pinfunction "PWMTYP_9") (pintype "input"))
      (node (ref "U202") (pin "15") (pinfunction "VSS_15") (pintype "passive"))
      (node (ref "U202") (pin "2") (pinfunction "COM_2") (pintype "passive"))
      (node (ref "U203") (pin "15") (pinfunction "VSS_15") (pintype "passive"))
      (node (ref "U203") (pin "2") (pinfunction "COM_2") (pintype "passive"))
    )
    (net (code "32") (name "Net-(D200-PadA)") (class "Default")
      (node (ref "D200") (pin "A") (pinfunction "A_A") (pintype "passive"))
      (node (ref "R218") (pin "1") (pinfunction "1_1") (pintype "passive"))
    )
    (net (code "33") (name "Net-(D201-C)") (class "Default")
      (node (ref "C205") (pin "2") (pinfunction "2_2") (pintype "passive"))
      (node (ref "D201") (pin "1") (pinfunction "C_1") (pintype "passive"))
      (node (ref "U202") (pin "7") (pinfunction "VB_7") (pintype "passive"))
    )
    (net (code "34") (name "Net-(D202-C)") (class "Default")
      (node (ref "C206") (pin "2") (pinfunction "2_2") (pintype "passive"))
      (node (ref "D202") (pin "1") (pinfunction "C_1") (pintype "passive"))
      (node (ref "U203") (pin "7") (pinfunction "VB_7") (pintype "passive"))
    )
    (net (code "35") (name "Net-(Q200-B)") (class "Default")
      (node (ref "Q200") (pin "1") (pinfunction "B_1") (pintype "passive"))
      (node (ref "R207") (pin "1") (pinfunction "1_1") (pintype "passive"))
    )
    (net (code "36") (name "Net-(Q201-B)") (class "Default")
      (node (ref "Q201") (pin "2") (pinfunction "B_2") (pintype "passive"))
      (node (ref "R215") (pin "2") (pinfunction "2_2") (pintype "passive"))
    )
    (net (code "37") (name "Net-(Q202-B)") (class "Default")
      (node (ref "Q202") (pin "2") (pinfunction "B_2") (pintype "passive"))
      (node (ref "R217") (pin "2") (pinfunction "2_2") (pintype "passive"))
    )
    (net (code "38") (name "Net-(Q203-B)") (class "Default")
      (node (ref "Q203") (pin "2") (pinfunction "B_2") (pintype "passive"))
      (node (ref "R220") (pin "2") (pinfunction "2_2") (pintype "passive"))
    )
    (net (code "39") (name "Net-(Q204-B)") (class "Default")
      (node (ref "Q204") (pin "2") (pinfunction "B_2") (pintype "passive"))
      (node (ref "R222") (pin "2") (pinfunction "2_2") (pintype "passive"))
    )
    (net (code "40") (name "Net-(S201-NO)") (class "Default")
      (node (ref "J200") (pin "6") (pinfunction "6_6") (pintype "passive"))
      (node (ref "S201") (pin "3") (pinfunction "NO_3") (pintype "passive"))
    )
    (net (code "41") (name "Net-(S202-COM)") (class "Default")
      (node (ref "S202") (pin "2") (pinfunction "COM_2") (pintype "passive"))
      (node (ref "U201") (pin "1") (pinfunction "DT1_1") (pintype "input"))
    )
    (net (code "42") (name "Net-(S203-COM)") (class "Default")
      (node (ref "S203") (pin "2") (pinfunction "COM_2") (pintype "passive"))
      (node (ref "U201") (pin "2") (pinfunction "DT0_2") (pintype "input"))
    )
    (net (code "43") (name "Net-(S204-COM)") (class "Default")
      (node (ref "S204") (pin "2") (pinfunction "COM_2") (pintype "passive"))
      (node (ref "U201") (pin "18") (pinfunction "FREQSEL0_18") (pintype "input"))
    )
    (net (code "44") (name "Net-(S205-COM)") (class "Default")
      (node (ref "S205") (pin "2") (pinfunction "COM_2") (pintype "passive"))
      (node (ref "U201") (pin "21") (pinfunction "SST_21") (pintype "input"))
    )
    (net (code "45") (name "Net-(U200-1IN+)") (class "Default")
      (node (ref "C215") (pin "2") (pinfunction "2_2") (pintype "passive"))
      (node (ref "R200") (pin "1") (pinfunction "1_1") (pintype "passive"))
      (node (ref "R201") (pin "2") (pinfunction "2_2") (pintype "passive"))
      (node (ref "R203") (pin "1") (pinfunction "1_1") (pintype "passive"))
      (node (ref "U200") (pin "3") (pinfunction "1IN+_3") (pintype "passive"))
      (node (ref "U200") (pin "6") (pinfunction "2IN-_6") (pintype "passive"))
    )
    (net (code "46") (name "Net-(U200-1IN-)") (class "Default")
      (node (ref "C204") (pin "2") (pinfunction "2_2") (pintype "passive"))
      (node (ref "R206") (pin "1") (pinfunction "1_1") (pintype "passive"))
      (node (ref "R209") (pin "2") (pinfunction "2_2") (pintype "passive"))
      (node (ref "U200") (pin "2") (pinfunction "1IN-_2") (pintype "passive"))
      (node (ref "U200") (pin "5") (pinfunction "2IN+_5") (pintype "passive"))
    )
    (net (code "47") (name "Net-(U200-2OUT)") (class "Default")
      (node (ref "C202") (pin "2") (pinfunction "2_2") (pintype "passive"))
      (node (ref "R202") (pin "1") (pinfunction "1_1") (pintype "passive"))
      (node (ref "R205") (pin "2") (pinfunction "2_2") (pintype "passive"))
      (node (ref "U200") (pin "7") (pinfunction "2OUT_7") (pintype "passive"))
    )
    (net (code "48") (name "Net-(U201A-LEDOUT)") (class "Default")
      (node (ref "D200") (pin "C") (pinfunction "C_C") (pintype "passive"))
      (node (ref "U201") (pin "8") (pinfunction "LEDOUT_8") (pintype "output"))
    )
    (net (code "49") (name "Net-(U201A-OSC1)") (class "Default")
      (node (ref "C220") (pin "1") (pinfunction "1_1") (pintype "passive"))
      (node (ref "U201") (pin "10") (pinfunction "OSC1_10") (pintype "input"))
      (node (ref "Y200") (pin "2") (pinfunction "2_2") (pintype "passive"))
    )
    (net (code "50") (name "Net-(U201A-OSC2)") (class "Default")
      (node (ref "C223") (pin "1") (pinfunction "1_1") (pintype "passive"))
      (node (ref "U201") (pin "11") (pinfunction "OSC2_11") (pintype "output"))
      (node (ref "Y200") (pin "1") (pinfunction "1_1") (pintype "passive"))
    )
    (net (code "51") (name "unconnected-(J200-Pad8)") (class "Default")
      (node (ref "J200") (pin "8") (pinfunction "8_8") (pintype "passive+no_connect"))
    )
    (net (code "52") (name "unconnected-(S200-MNT_1-Pad4)") (class "Default")
      (node (ref "S200") (pin "4") (pinfunction "MNT_1_4") (pintype "passive"))
    )
    (net (code "53") (name "unconnected-(S200-MNT_2-Pad5)") (class "Default")
      (node (ref "S200") (pin "5") (pinfunction "MNT_2_5") (pintype "passive"))
    )
    (net (code "54") (name "unconnected-(S201-NC-Pad1)") (class "Default")
      (node (ref "S201") (pin "1") (pinfunction "NC_1") (pintype "passive"))
    )
    (net (code "55") (name "unconnected-(S201-PadMH1)") (class "Default")
      (node (ref "S201") (pin "MH1") (pinfunction "MH1_MH1") (pintype "passive"))
    )
    (net (code "56") (name "unconnected-(S201-PadMH2)") (class "Default")
      (node (ref "S201") (pin "MH2") (pinfunction "MH2_MH2") (pintype "passive"))
    )
    (net (code "57") (name "unconnected-(S202-PadMH1)") (class "Default")
      (node (ref "S202") (pin "MH1") (pinfunction "MH1_MH1") (pintype "passive"))
    )
    (net (code "58") (name "unconnected-(S202-PadMH2)") (class "Default")
      (node (ref "S202") (pin "MH2") (pinfunction "MH2_MH2") (pintype "passive"))
    )
    (net (code "59") (name "unconnected-(S203-PadMH1)") (class "Default")
      (node (ref "S203") (pin "MH1") (pinfunction "MH1_MH1") (pintype "passive"))
    )
    (net (code "60") (name "unconnected-(S203-PadMH2)") (class "Default")
      (node (ref "S203") (pin "MH2") (pinfunction "MH2_MH2") (pintype "passive"))
    )
    (net (code "61") (name "unconnected-(S204-PadMH1)") (class "Default")
      (node (ref "S204") (pin "MH1") (pinfunction "MH1_MH1") (pintype "passive"))
    )
    (net (code "62") (name "unconnected-(S204-PadMH2)") (class "Default")
      (node (ref "S204") (pin "MH2") (pinfunction "MH2_MH2") (pintype "passive"))
    )
    (net (code "63") (name "unconnected-(S205-PadMH1)") (class "Default")
      (node (ref "S205") (pin "MH1") (pinfunction "MH1_MH1") (pintype "passive"))
    )
    (net (code "64") (name "unconnected-(S205-PadMH2)") (class "Default")
      (node (ref "S205") (pin "MH2") (pinfunction "MH2_MH2") (pintype "passive"))
    )
    (net (code "65") (name "unconnected-(U201A-RXD-Pad4)") (class "Default")
      (node (ref "U201") (pin "4") (pinfunction "RXD_4") (pintype "input+no_connect"))
    )
    (net (code "66") (name "unconnected-(U201B-NC-Pad22)") (class "Default")
      (node (ref "U201") (pin "22") (pinfunction "NC_22") (pintype "passive+no_connect"))
    )
    (net (code "67") (name "unconnected-(U202-N.C._1-Pad4)") (class "Default")
      (node (ref "U202") (pin "4") (pinfunction "N.C._1_4") (pintype "passive+no_connect"))
    )
    (net (code "68") (name "unconnected-(U202-N.C._2-Pad5)") (class "Default")
      (node (ref "U202") (pin "5") (pinfunction "N.C._2_5") (pintype "passive+no_connect"))
    )
    (net (code "69") (name "unconnected-(U202-N.C._3-Pad9)") (class "Default")
      (node (ref "U202") (pin "9") (pinfunction "N.C._3_9") (pintype "passive+no_connect"))
    )
    (net (code "70") (name "unconnected-(U202-N.C._4-Pad10)") (class "Default")
      (node (ref "U202") (pin "10") (pinfunction "N.C._4_10") (pintype "passive+no_connect"))
    )
    (net (code "71") (name "unconnected-(U202-N.C._5-Pad16)") (class "Default")
      (node (ref "U202") (pin "16") (pinfunction "N.C._5_16") (pintype "passive+no_connect"))
    )
    (net (code "72") (name "unconnected-(U203-N.C._1-Pad4)") (class "Default")
      (node (ref "U203") (pin "4") (pinfunction "N.C._1_4") (pintype "passive+no_connect"))
    )
    (net (code "73") (name "unconnected-(U203-N.C._2-Pad5)") (class "Default")
      (node (ref "U203") (pin "5") (pinfunction "N.C._2_5") (pintype "passive+no_connect"))
    )
    (net (code "74") (name "unconnected-(U203-N.C._3-Pad9)") (class "Default")
      (node (ref "U203") (pin "9") (pinfunction "N.C._3_9") (pintype "passive+no_connect"))
    )
    (net (code "75") (name "unconnected-(U203-N.C._4-Pad10)") (class "Default")
      (node (ref "U203") (pin "10") (pinfunction "N.C._4_10") (pintype "passive+no_connect"))
    )
    (net (code "76") (name "unconnected-(U203-N.C._5-Pad16)") (class "Default")
      (node (ref "U203") (pin "16") (pinfunction "N.C._5_16") (pintype "passive+no_connect"))
    )
  )
)
